# Sim800.net
KiCad netlist of a schematic drawn in Altium Designer
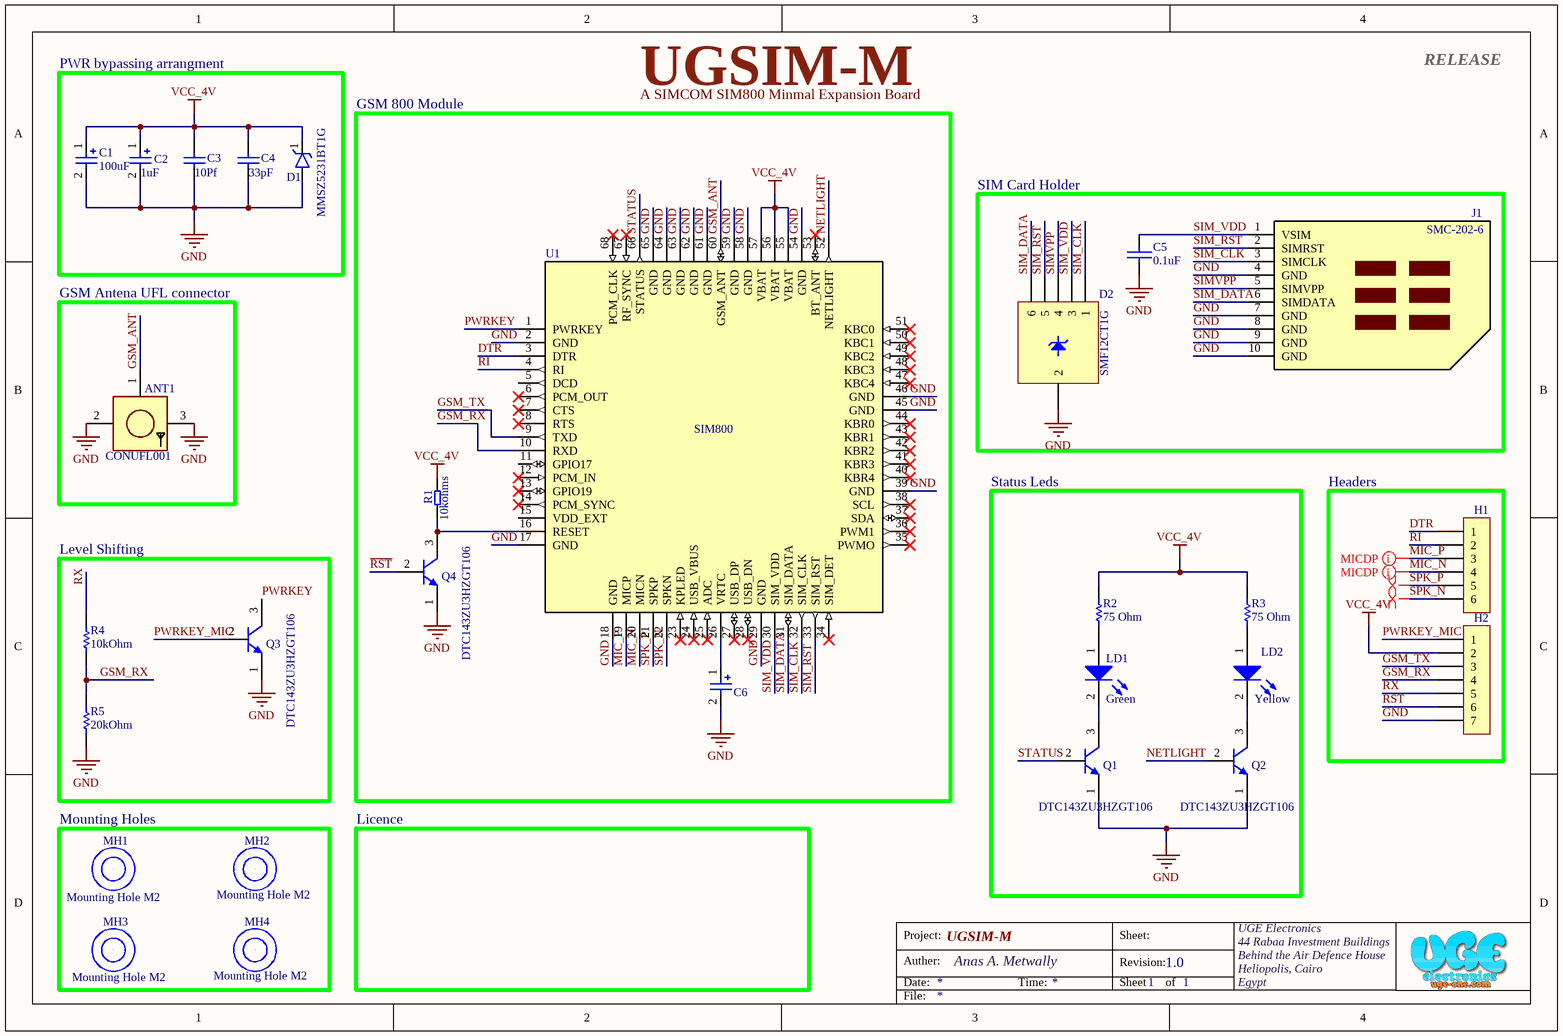
[diagram p0: Sim800.SchDoc]

(export (version "E")
  (design (tool "Eeschema 10.0.6"))
  (components
    (comp (ref "ANT1")
      (value "CONUFL001")
      (footprint "UFL")
      (description "CONN UMC JACK STR SMD")
      (fields
        (field (name "MANUFACTURER") "Linx")
        (field (name "MANUFACTURER PART NUMBER") "CONUFL001-SMD-T")
      )
      (libsource (lib "Sim800board") (part "CONUFL001-SMD-T"))
    )
    (comp (ref "C1")
      (value "100uF")
      (footprint "Tanat Case D")
      (fields
        (field (name "MANUFACTURER") "Kyocera AVX")
        (field (name "MANUFACTURER PART NUMBER") "TAJA105K035TNJ")
        (field (name "TOLERANCE") "20%")
      )
      (libsource (lib "Sim800board") (part "Cap 100uF Tant"))
    )
    (comp (ref "C2")
      (value "1uF")
      (footprint "C1206")
      (description "1µF Molded Tantalum Capacitors 35V 1206 (3216 Metric) 7.5Ohm @ 100kHz")
      (fields
        (field (name "MANUFACTURER") "Kyocera AVX")
        (field (name "MANUFACTURER PART NUMBER") "TAJA105K035TNJ")
      )
      (libsource (lib "Sim800board") (part "Cap 1uF Tant 1206"))
    )
    (comp (ref "C3")
      (value "10Pf")
      (footprint "0603Cap")
      (description "Multilayer Ceramic Capacitors MLCC - SMD/SMT 16V 10pF 0603 X7R 0.1")
      (fields
        (field (name "MANUFACTURER") "KEMET")
        (field (name "MANUFACTURER PART NUMBER") "C0603C100K4RACTU")
      )
      (libsource (lib "Sim800board") (part "Cap 10pf 0603"))
    )
    (comp (ref "C4")
      (value "33pF")
      (description "Multilayer Ceramic Capacitors MLCC - SMD/SMT 50V 33pF 0603 X8R 20%")
      (fields
        (field (name "MANUFACTURER") "KEMET")
        (field (name "MANUFACTURER PART NUMBER") "C0603C330M5HACTU")
      )
      (libsource (lib "Sim800board") (part "Cap 33pF 0603"))
    )
    (comp (ref "C5")
      (value "0.1uF")
      (footprint "0603Cap")
      (description "Cap Ceramic 0.1uF 50V X7R 5% SMD 0603 125C Paper T/R. CC0603JPX7R9BB104")
      (fields
        (field (name "MANUFACTURER") "Yageo")
        (field (name "MANUFACTURER PART NUMBER") "CC0603JPX7R9BB104")
      )
      (libsource (lib "Sim800board") (part "Cap 0.1uF 50V 0603 X7R"))
    )
    (comp (ref "C6")
      (value "4.7uF")
      (footprint "C1206")
      (description "CAP TANT 4.7UF 10% 16V 1206,TAJA475K016RNJ")
      (fields
        (field (name "MANUFACTURER") "Kyocera AVX")
        (field (name "MANUFACTURER PART NUMBER") "TAJA475K016RNJ")
      )
      (libsource (lib "Sim800board") (part "Cap 4.7uF tantalum"))
    )
    (comp (ref "D1")
      (value "MMSZ5231BT1G")
      (footprint "SOD-123")
      (description "DIODE ZENER 5.1V 500MW SOD123")
      (fields (field (name "MANUFACTURER") "ON Semiconductor") (field (name "TOLERANCE") "5%"))
      (libsource (lib "Sim800board") (part "MMSZ5231BT1G"))
    )
    (comp (ref "D2")
      (value "SMF12CT1G")
      (footprint "SOT-363")
      (description "TVS DIODE 12V 23V SC88")
      (fields (field (name "MANUFACTURER") "ON Semiconductor"))
      (libsource (lib "Sim800board") (part "SMF12CT1G"))
    )
    (comp (ref "H1")
      (value "Heder 6X1")
      (footprint "Header6X1")
      (libsource (lib "Sim800board") (part "Heder 6X1"))
    )
    (comp (ref "H2")
      (value "Heder 7X1")
      (footprint "Header 7X1")
      (libsource (lib "Sim800board") (part "Heder 7X1"))
    )
    (comp (ref "J1")
      (value "SMC-202-6")
      (footprint "Micro SIM Connector")
      (libsource (lib "Sim800board") (part "Micro Sim Connector"))
    )
    (comp (ref "LD1")
      (value "Green")
      (footprint "0603D-G")
      (description "LED GREEN DIFFUSED 0603 SMD")
      (fields (field (name "MANUFACTURER") "Rohm") (field (name "MANUFACTURER PART NUMBER") "SML-D12M8WT86"))
      (libsource (lib "Sim800board") (part "LED Green"))
    )
    (comp (ref "LD2")
      (value "Yellow")
      (footprint "0603D-y")
      (description "LED YELLOW DIFFUSED 0603 SMD")
      (fields (field (name "MANUFACTURER") "Rohm") (field (name "MANUFACTURER PART NUMBER") "SML-D12Y8WT86"))
      (libsource (lib "Sim800board") (part "LED Yellow"))
    )
    (comp (ref "MH1")
      (value "Mounting Hole M2")
      (footprint "M2Hole")
      (libsource (lib "Sim800board") (part "M2Hole"))
    )
    (comp (ref "MH2")
      (value "Mounting Hole M2")
      (footprint "M2Hole")
      (libsource (lib "Sim800board") (part "M2Hole"))
    )
    (comp (ref "MH3")
      (value "Mounting Hole M2")
      (footprint "M2Hole")
      (libsource (lib "Sim800board") (part "M2Hole"))
    )
    (comp (ref "MH4")
      (value "Mounting Hole M2")
      (footprint "M2Hole")
      (libsource (lib "Sim800board") (part "M2Hole"))
    )
    (comp (ref "Q1")
      (value "DTC143ZU3HZGT106")
      (footprint "Sot 323")
      (fields (field (name "MANUFACTURER") "Rohm"))
      (libsource (lib "Sim800board") (part "NPN Transistor Prebaised"))
    )
    (comp (ref "Q2")
      (value "DTC143ZU3HZGT106")
      (footprint "Sot 323")
      (fields (field (name "MANUFACTURER") "Rohm"))
      (libsource (lib "Sim800board") (part "NPN Transistor Prebaised"))
    )
    (comp (ref "Q3")
      (value "DTC143ZU3HZGT106")
      (footprint "Sot 323")
      (fields (field (name "MANUFACTURER") "Rohm"))
      (libsource (lib "Sim800board") (part "NPN Transistor Prebaised"))
    )
    (comp (ref "Q4")
      (value "DTC143ZU3HZGT106")
      (footprint "Sot 323")
      (fields (field (name "MANUFACTURER") "Rohm"))
      (libsource (lib "Sim800board") (part "NPN Transistor Prebaised"))
    )
    (comp (ref "R1")
      (value "10kohms")
      (footprint "0603R")
      (libsource (lib "Sim800board") (part "Res 10Kohms"))
    )
    (comp (ref "R2")
      (value "75 Ohm")
      (footprint "0603R")
      (fields
        (field (name "MANUFACTURER") "Rohm")
        (field (name "MANUFACTURER PART NUMBER") "ESR03EZPJ131")
        (field (name "TOLERANCE") "5%")
      )
      (libsource (lib "Sim800board") (part "RES 75 Ohm 0603"))
    )
    (comp (ref "R3")
      (value "75 Ohm")
      (footprint "0603R")
      (fields
        (field (name "MANUFACTURER") "Rohm")
        (field (name "MANUFACTURER PART NUMBER") "ESR03EZPJ131")
        (field (name "TOLERANCE") "5%")
      )
      (libsource (lib "Sim800board") (part "RES 75 Ohm 0603"))
    )
    (comp (ref "R4")
      (value "10kOhm")
      (footprint "0603R")
      (description "RES SMD 10K OHM 1% 1/4W 0603")
      (fields (field (name "MANUFACTURER") "Rohm") (field (name "MANUFACTURER PART NUMBER") "ESR03EZPF1002"))
      (libsource (lib "Sim800board") (part "RES 10kOhms 0603"))
    )
    (comp (ref "R5")
      (value "20kOhm")
      (footprint "0603R")
      (description "RES SMD 10K OHM 1% 1/4W 0603")
      (fields (field (name "MANUFACTURER") "Rohm") (field (name "MANUFACTURER PART NUMBER") "ESR03EZPF1002"))
      (libsource (lib "Sim800board") (part "RES 20kOhms 0603"))
    )
    (comp (ref "U1")
      (value "SIM800")
      (footprint "SIMCom_SIM800")
      (libsource (lib "Sim800board") (part "SIM800"))
    )
  )
  (nets
    (net (code "1") (name "/DTR") (class "Default")
      (node (ref "H1") (pin "1") (pinfunction "1_1") (pintype "passive"))
      (node (ref "U1") (pin "3") (pinfunction "DTR_3") (pintype "passive"))
    )
    (net (code "2") (name "/GSM_ANT") (class "Default")
      (node (ref "ANT1") (pin "1") (pinfunction "1_1") (pintype "passive"))
      (node (ref "U1") (pin "60") (pinfunction "GSM_ANT_60") (pintype "bidirectional"))
    )
    (net (code "3") (name "/GSM_RX") (class "Default")
      (node (ref "H2") (pin "4") (pinfunction "4_4") (pintype "passive"))
      (node (ref "R4") (pin "1") (pinfunction "1_1") (pintype "passive"))
      (node (ref "R5") (pin "2") (pinfunction "2_2") (pintype "passive"))
      (node (ref "U1") (pin "10") (pinfunction "RXD_10") (pintype "passive"))
    )
    (net (code "4") (name "/GSM_TX") (class "Default")
      (node (ref "H2") (pin "3") (pinfunction "3_3") (pintype "passive"))
      (node (ref "U1") (pin "9") (pinfunction "TXD_9") (pintype "output"))
    )
    (net (code "5") (name "/MIC_N") (class "Default")
      (node (ref "H1") (pin "4") (pinfunction "4_4") (pintype "passive"))
      (node (ref "U1") (pin "20") (pinfunction "MICN_20") (pintype "passive"))
    )
    (net (code "6") (name "/MIC_P") (class "Default")
      (node (ref "H1") (pin "3") (pinfunction "3_3") (pintype "passive"))
      (node (ref "U1") (pin "19") (pinfunction "MICP_19") (pintype "passive"))
    )
    (net (code "7") (name "/NETLIGHT") (class "Default")
      (node (ref "Q2") (pin "2") (pinfunction "B_2") (pintype "passive"))
      (node (ref "U1") (pin "52") (pinfunction "NETLIGHT_52") (pintype "output"))
    )
    (net (code "8") (name "/PWRKEY") (class "Default")
      (node (ref "Q3") (pin "3") (pinfunction "C_3") (pintype "passive"))
      (node (ref "U1") (pin "1") (pinfunction "PWRKEY_1") (pintype "power_in"))
    )
    (net (code "9") (name "/PWRKEY_MIC") (class "Default")
      (node (ref "H2") (pin "1") (pinfunction "1_1") (pintype "passive"))
      (node (ref "Q3") (pin "2") (pinfunction "B_2") (pintype "passive"))
    )
    (net (code "10") (name "/RI") (class "Default")
      (node (ref "H1") (pin "2") (pinfunction "2_2") (pintype "passive"))
      (node (ref "U1") (pin "4") (pinfunction "RI_4") (pintype "output"))
    )
    (net (code "11") (name "/RX") (class "Default")
      (node (ref "H2") (pin "5") (pinfunction "5_5") (pintype "passive"))
      (node (ref "R4") (pin "2") (pinfunction "2_2") (pintype "passive"))
    )
    (net (code "12") (name "/SIMVPP") (class "Default")
      (node (ref "D2") (pin "4") (pinfunction "4_4") (pintype "passive"))
      (node (ref "J1") (pin "5") (pinfunction "SIMVPP_5") (pintype "passive"))
    )
    (net (code "13") (name "/SIM_CLK") (class "Default")
      (node (ref "D2") (pin "1") (pinfunction "1_1") (pintype "passive"))
      (node (ref "J1") (pin "3") (pinfunction "SIMCLK_3") (pintype "passive"))
      (node (ref "U1") (pin "32") (pinfunction "SIM_CLK_32") (pintype "output"))
    )
    (net (code "14") (name "/SIM_DATA") (class "Default")
      (node (ref "D2") (pin "6") (pinfunction "6_6") (pintype "passive"))
      (node (ref "J1") (pin "6") (pinfunction "SIMDATA_6") (pintype "passive"))
      (node (ref "U1") (pin "31") (pinfunction "SIM_DATA_31") (pintype "bidirectional"))
    )
    (net (code "15") (name "/SIM_RST") (class "Default")
      (node (ref "D2") (pin "5") (pinfunction "5_5") (pintype "passive"))
      (node (ref "J1") (pin "2") (pinfunction "SIMRST_2") (pintype "passive"))
      (node (ref "U1") (pin "33") (pinfunction "SIM_RST_33") (pintype "output"))
    )
    (net (code "16") (name "/SIM_VDD") (class "Default")
      (node (ref "C5") (pin "1") (pinfunction "1_1") (pintype "passive"))
      (node (ref "D2") (pin "3") (pinfunction "3_3") (pintype "passive"))
      (node (ref "J1") (pin "1") (pinfunction "VSIM_1") (pintype "passive"))
      (node (ref "U1") (pin "30") (pinfunction "SIM_VDD_30") (pintype "power_in"))
    )
    (net (code "17") (name "/SPK_N") (class "Default")
      (node (ref "H1") (pin "6") (pinfunction "6_6") (pintype "passive"))
      (node (ref "U1") (pin "22") (pinfunction "SPKN_22") (pintype "passive"))
    )
    (net (code "18") (name "/SPK_P") (class "Default")
      (node (ref "H1") (pin "5") (pinfunction "5_5") (pintype "passive"))
      (node (ref "U1") (pin "21") (pinfunction "SPKP_21") (pintype "passive"))
    )
    (net (code "19") (name "/STATUS") (class "Default")
      (node (ref "Q1") (pin "2") (pinfunction "B_2") (pintype "passive"))
      (node (ref "U1") (pin "66") (pinfunction "STATUS_66") (pintype "output"))
    )
    (net (code "20") (name "/~{RST}") (class "Default")
      (node (ref "H2") (pin "6") (pinfunction "6_6") (pintype "passive"))
      (node (ref "Q4") (pin "2") (pinfunction "B_2") (pintype "passive"))
    )
    (net (code "21") (name "GND") (class "Default")
      (node (ref "ANT1") (pin "2") (pinfunction "2_2") (pintype "passive"))
      (node (ref "ANT1") (pin "3") (pinfunction "3_3") (pintype "passive"))
      (node (ref "C1") (pin "2") (pinfunction "2_2") (pintype "passive"))
      (node (ref "C2") (pin "2") (pinfunction "2_2") (pintype "passive"))
      (node (ref "C3") (pin "1") (pinfunction "1_1") (pintype "passive"))
      (node (ref "C4") (pin "1") (pinfunction "1_1") (pintype "passive"))
      (node (ref "C5") (pin "2") (pinfunction "2_2") (pintype "passive"))
      (node (ref "C6") (pin "2") (pinfunction "2_2") (pintype "passive"))
      (node (ref "D1") (pin "2") (pinfunction "2_2") (pintype "passive"))
      (node (ref "D2") (pin "2") (pinfunction "2_2") (pintype "passive"))
      (node (ref "H2") (pin "7") (pinfunction "7_7") (pintype "passive"))
      (node (ref "J1") (pin "10") (pinfunction "GND_10") (pintype "passive"))
      (node (ref "J1") (pin "4") (pinfunction "GND_4") (pintype "passive"))
      (node (ref "J1") (pin "7") (pinfunction "GND_7") (pintype "passive"))
      (node (ref "J1") (pin "8") (pinfunction "GND_8") (pintype "passive"))
      (node (ref "J1") (pin "9") (pinfunction "GND_9") (pintype "passive"))
      (node (ref "Q1") (pin "1") (pinfunction "E_1") (pintype "passive"))
      (node (ref "Q2") (pin "1") (pinfunction "E_1") (pintype "passive"))
      (node (ref "Q3") (pin "1") (pinfunction "E_1") (pintype "passive"))
      (node (ref "Q4") (pin "1") (pinfunction "E_1") (pintype "passive"))
      (node (ref "R5") (pin "1") (pinfunction "1_1") (pintype "passive"))
      (node (ref "U1") (pin "17") (pinfunction "GND_17") (pintype "power_in"))
      (node (ref "U1") (pin "18") (pinfunction "GND_18") (pintype "power_in"))
      (node (ref "U1") (pin "2") (pinfunction "GND_2") (pintype "power_in"))
      (node (ref "U1") (pin "29") (pinfunction "GND_29") (pintype "power_in"))
      (node (ref "U1") (pin "39") (pinfunction "GND_39") (pintype "power_in"))
      (node (ref "U1") (pin "45") (pinfunction "GND_45") (pintype "power_in"))
      (node (ref "U1") (pin "46") (pinfunction "GND_46") (pintype "power_in"))
      (node (ref "U1") (pin "54") (pinfunction "GND_54") (pintype "power_in"))
      (node (ref "U1") (pin "58") (pinfunction "GND_58") (pintype "power_in"))
      (node (ref "U1") (pin "59") (pinfunction "GND_59") (pintype "power_in"))
      (node (ref "U1") (pin "61") (pinfunction "GND_61") (pintype "power_in"))
      (node (ref "U1") (pin "62") (pinfunction "GND_62") (pintype "power_in"))
      (node (ref "U1") (pin "63") (pinfunction "GND_63") (pintype "power_in"))
      (node (ref "U1") (pin "64") (pinfunction "GND_64") (pintype "power_in"))
      (node (ref "U1") (pin "65") (pinfunction "GND_65") (pintype "power_in"))
    )
    (net (code "22") (name "Net-(LD1-A)") (class "Default")
      (node (ref "LD1") (pin "1") (pinfunction "A_1") (pintype "passive"))
      (node (ref "R2") (pin "2") (pinfunction "2_2") (pintype "passive"))
    )
    (net (code "23") (name "Net-(LD1-K)") (class "Default")
      (node (ref "LD1") (pin "2") (pinfunction "K_2") (pintype "passive"))
      (node (ref "Q1") (pin "3") (pinfunction "C_3") (pintype "passive"))
    )
    (net (code "24") (name "Net-(LD2-A)") (class "Default")
      (node (ref "LD2") (pin "1") (pinfunction "A_1") (pintype "passive"))
      (node (ref "R3") (pin "2") (pinfunction "2_2") (pintype "passive"))
    )
    (net (code "25") (name "Net-(LD2-K)") (class "Default")
      (node (ref "LD2") (pin "2") (pinfunction "K_2") (pintype "passive"))
      (node (ref "Q2") (pin "3") (pinfunction "C_3") (pintype "passive"))
    )
    (net (code "26") (name "Net-(Q4-C)") (class "Default")
      (node (ref "Q4") (pin "3") (pinfunction "C_3") (pintype "passive"))
      (node (ref "R1") (pin "1") (pinfunction "1_1") (pintype "passive"))
      (node (ref "U1") (pin "16") (pinfunction "RESET_16") (pintype "passive"))
    )
    (net (code "27") (name "Net-(U1-VRTC)") (class "Default")
      (node (ref "C6") (pin "1") (pinfunction "1_1") (pintype "passive"))
      (node (ref "U1") (pin "26") (pinfunction "VRTC_26") (pintype "power_in"))
    )
    (net (code "28") (name "VCC_4V") (class "Default")
      (node (ref "C1") (pin "1") (pinfunction "1_1") (pintype "passive"))
      (node (ref "C2") (pin "1") (pinfunction "1_1") (pintype "passive"))
      (node (ref "C3") (pin "2") (pinfunction "2_2") (pintype "passive"))
      (node (ref "C4") (pin "2") (pinfunction "2_2") (pintype "passive"))
      (node (ref "D1") (pin "1") (pinfunction "1_1") (pintype "passive"))
      (node (ref "H2") (pin "2") (pinfunction "2_2") (pintype "passive"))
      (node (ref "R1") (pin "2") (pinfunction "2_2") (pintype "passive"))
      (node (ref "R2") (pin "1") (pinfunction "1_1") (pintype "passive"))
      (node (ref "R3") (pin "1") (pinfunction "1_1") (pintype "passive"))
      (node (ref "U1") (pin "55") (pinfunction "VBAT_55") (pintype "power_in"))
      (node (ref "U1") (pin "56") (pinfunction "VBAT_56") (pintype "power_in"))
      (node (ref "U1") (pin "57") (pinfunction "VBAT_57") (pintype "power_in"))
    )
    (net (code "29") (name "unconnected-(MH1-Pad0)") (class "Default")
      (node (ref "MH1") (pin "0") (pinfunction "0_0") (pintype "passive"))
    )
    (net (code "30") (name "unconnected-(MH2-Pad0)") (class "Default")
      (node (ref "MH2") (pin "0") (pinfunction "0_0") (pintype "passive"))
    )
    (net (code "31") (name "unconnected-(MH3-Pad0)") (class "Default")
      (node (ref "MH3") (pin "0") (pinfunction "0_0") (pintype "passive"))
    )
    (net (code "32") (name "unconnected-(MH4-Pad0)") (class "Default")
      (node (ref "MH4") (pin "0") (pinfunction "0_0") (pintype "passive"))
    )
    (net (code "33") (name "unconnected-(U1-ADC-Pad25)") (class "Default")
      (node (ref "U1") (pin "25") (pinfunction "ADC_25") (pintype "input+no_connect"))
    )
    (net (code "34") (name "unconnected-(U1-BT_ANT-Pad53)") (class "Default")
      (node (ref "U1") (pin "53") (pinfunction "BT_ANT_53") (pintype "bidirectional+no_connect"))
    )
    (net (code "35") (name "unconnected-(U1-CTS-Pad7)") (class "Default")
      (node (ref "U1") (pin "7") (pinfunction "CTS_7") (pintype "output+no_connect"))
    )
    (net (code "36") (name "unconnected-(U1-DCD-Pad5)") (class "Default")
      (node (ref "U1") (pin "5") (pinfunction "DCD_5") (pintype "output"))
    )
    (net (code "37") (name "unconnected-(U1-GPIO17-Pad11)") (class "Default")
      (node (ref "U1") (pin "11") (pinfunction "GPIO17_11") (pintype "bidirectional"))
    )
    (net (code "38") (name "unconnected-(U1-GPIO19-Pad13)") (class "Default")
      (node (ref "U1") (pin "13") (pinfunction "GPIO19_13") (pintype "bidirectional+no_connect"))
    )
    (net (code "39") (name "unconnected-(U1-KBC0-Pad51)") (class "Default")
      (node (ref "U1") (pin "51") (pinfunction "KBC0_51") (pintype "input+no_connect"))
    )
    (net (code "40") (name "unconnected-(U1-KBC1-Pad50)") (class "Default")
      (node (ref "U1") (pin "50") (pinfunction "KBC1_50") (pintype "input+no_connect"))
    )
    (net (code "41") (name "unconnected-(U1-KBC2-Pad49)") (class "Default")
      (node (ref "U1") (pin "49") (pinfunction "KBC2_49") (pintype "input+no_connect"))
    )
    (net (code "42") (name "unconnected-(U1-KBC3-Pad48)") (class "Default")
      (node (ref "U1") (pin "48") (pinfunction "KBC3_48") (pintype "input+no_connect"))
    )
    (net (code "43") (name "unconnected-(U1-KBC4-Pad47)") (class "Default")
      (node (ref "U1") (pin "47") (pinfunction "KBC4_47") (pintype "input+no_connect"))
    )
    (net (code "44") (name "unconnected-(U1-KBR0-Pad44)") (class "Default")
      (node (ref "U1") (pin "44") (pinfunction "KBR0_44") (pintype "output+no_connect"))
    )
    (net (code "45") (name "unconnected-(U1-KBR1-Pad43)") (class "Default")
      (node (ref "U1") (pin "43") (pinfunction "KBR1_43") (pintype "output+no_connect"))
    )
    (net (code "46") (name "unconnected-(U1-KBR2-Pad42)") (class "Default")
      (node (ref "U1") (pin "42") (pinfunction "KBR2_42") (pintype "output+no_connect"))
    )
    (net (code "47") (name "unconnected-(U1-KBR3-Pad41)") (class "Default")
      (node (ref "U1") (pin "41") (pinfunction "KBR3_41") (pintype "output+no_connect"))
    )
    (net (code "48") (name "unconnected-(U1-KBR4-Pad40)") (class "Default")
      (node (ref "U1") (pin "40") (pinfunction "KBR4_40") (pintype "output+no_connect"))
    )
    (net (code "49") (name "unconnected-(U1-KPLED-Pad23)") (class "Default")
      (node (ref "U1") (pin "23") (pinfunction "KPLED_23") (pintype "input+no_connect"))
    )
    (net (code "50") (name "unconnected-(U1-PCM_CLK-Pad68)") (class "Default")
      (node (ref "U1") (pin "68") (pinfunction "PCM_CLK_68") (pintype "input+no_connect"))
    )
    (net (code "51") (name "unconnected-(U1-PCM_IN-Pad12)") (class "Default")
      (node (ref "U1") (pin "12") (pinfunction "PCM_IN_12") (pintype "input+no_connect"))
    )
    (net (code "52") (name "unconnected-(U1-PCM_OUT-Pad6)") (class "Default")
      (node (ref "U1") (pin "6") (pinfunction "PCM_OUT_6") (pintype "output+no_connect"))
    )
    (net (code "53") (name "unconnected-(U1-PCM_SYNC-Pad14)") (class "Default")
      (node (ref "U1") (pin "14") (pinfunction "PCM_SYNC_14") (pintype "output+no_connect"))
    )
    (net (code "54") (name "unconnected-(U1-PWM1-Pad36)") (class "Default")
      (node (ref "U1") (pin "36") (pinfunction "PWM1_36") (pintype "output+no_connect"))
    )
    (net (code "55") (name "unconnected-(U1-PWMO-Pad35)") (class "Default")
      (node (ref "U1") (pin "35") (pinfunction "PWMO_35") (pintype "output+no_connect"))
    )
    (net (code "56") (name "unconnected-(U1-RF_SYNC-Pad67)") (class "Default")
      (node (ref "U1") (pin "67") (pinfunction "RF_SYNC_67") (pintype "input+no_connect"))
    )
    (net (code "57") (name "unconnected-(U1-RTS-Pad8)") (class "Default")
      (node (ref "U1") (pin "8") (pinfunction "RTS_8") (pintype "passive+no_connect"))
    )
    (net (code "58") (name "unconnected-(U1-SCL-Pad38)") (class "Default")
      (node (ref "U1") (pin "38") (pinfunction "SCL_38") (pintype "output+no_connect"))
    )
    (net (code "59") (name "unconnected-(U1-SDA-Pad37)") (class "Default")
      (node (ref "U1") (pin "37") (pinfunction "SDA_37") (pintype "bidirectional+no_connect"))
    )
    (net (code "60") (name "unconnected-(U1-SIM_DET-Pad34)") (class "Default")
      (node (ref "U1") (pin "34") (pinfunction "SIM_DET_34") (pintype "input+no_connect"))
    )
    (net (code "61") (name "unconnected-(U1-USB_DN-Pad28)") (class "Default")
      (node (ref "U1") (pin "28") (pinfunction "USB_DN_28") (pintype "bidirectional+no_connect"))
    )
    (net (code "62") (name "unconnected-(U1-USB_DP-Pad27)") (class "Default")
      (node (ref "U1") (pin "27") (pinfunction "USB_DP_27") (pintype "bidirectional+no_connect"))
    )
    (net (code "63") (name "unconnected-(U1-USB_VBUS-Pad24)") (class "Default")
      (node (ref "U1") (pin "24") (pinfunction "USB_VBUS_24") (pintype "input+no_connect"))
    )
    (net (code "64") (name "unconnected-(U1-VDD_EXT-Pad15)") (class "Default")
      (node (ref "U1") (pin "15") (pinfunction "VDD_EXT_15") (pintype "power_in"))
    )
  )
)
